# watch_rev3.net
KiCad netlist of a schematic drawn in EAGLE
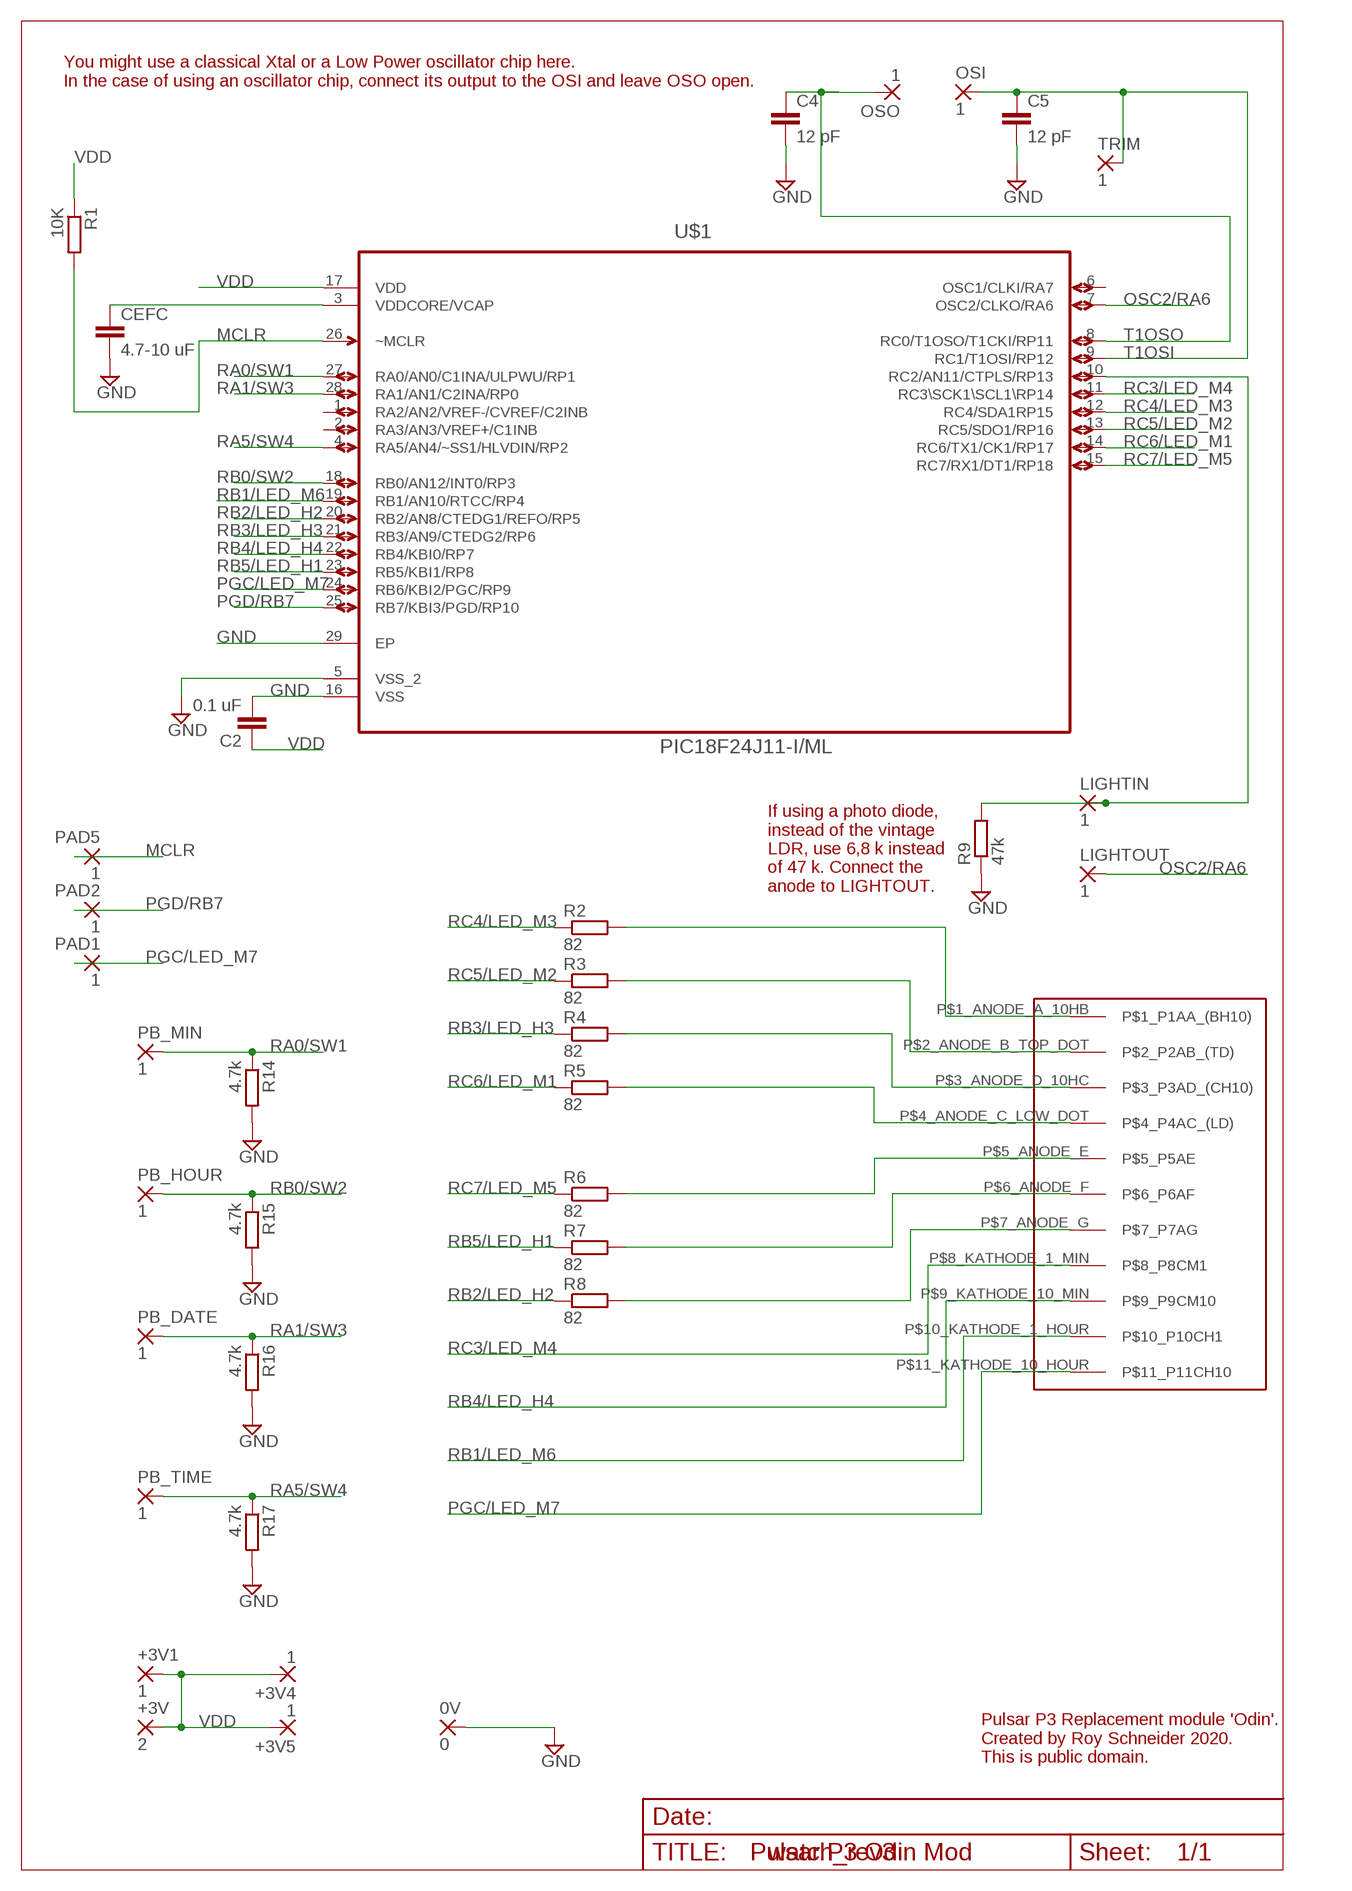
[diagram p0: schematic, sheet 1]

(export (version "E")
  (design (tool "Eeschema 10.0.6"))
  (components
    (comp (ref "+3V")
      (value "2")
      (footprint "eagle-import:SMD1,27-2,54")
      (libsource (lib "eagle-import") (part "SMD2"))
    )
    (comp (ref "+3V1")
      (value "1")
      (footprint "eagle-import:SMD1,27-2,54")
      (libsource (lib "eagle-import") (part "SMD2"))
    )
    (comp (ref "+3V4")
      (value "1")
      (footprint "eagle-import:SMD1,27-2,54")
      (libsource (lib "eagle-import") (part "SMD2"))
    )
    (comp (ref "+3V5")
      (value "1")
      (footprint "eagle-import:SMD1,27-2,54")
      (libsource (lib "eagle-import") (part "SMD2"))
    )
    (comp (ref "0V")
      (value "0")
      (footprint "eagle-import:SMD1,27-2,54")
      (libsource (lib "eagle-import") (part "SMD2"))
    )
    (comp (ref "C2")
      (value "0.1 uF")
      (footprint "eagle-import:C0603")
      (libsource (lib "eagle-import") (part "C-EUC0603"))
    )
    (comp (ref "C4")
      (value "12 pF")
      (footprint "eagle-import:C0603")
      (libsource (lib "eagle-import") (part "C-EUC0603"))
    )
    (comp (ref "C5")
      (value "12 pF")
      (footprint "eagle-import:C0603")
      (libsource (lib "eagle-import") (part "C-EUC0603"))
    )
    (comp (ref "CEFC")
      (value "4.7-10 uF")
      (footprint "eagle-import:C0603")
      (libsource (lib "eagle-import") (part "C-EUC0603"))
    )
    (comp (ref "LIGHTIN")
      (value "1")
      (footprint "eagle-import:SMD1,27-2,54")
      (libsource (lib "eagle-import") (part "SMD2"))
    )
    (comp (ref "LIGHTOUT")
      (value "1")
      (footprint "eagle-import:SMD1,27-2,54")
      (libsource (lib "eagle-import") (part "SMD2"))
    )
    (comp (ref "OSI")
      (value "1")
      (footprint "eagle-import:SMD1,27-2,54")
      (libsource (lib "eagle-import") (part "SMD2"))
    )
    (comp (ref "OSO")
      (value "1")
      (footprint "eagle-import:SMD1,27-2,54")
      (libsource (lib "eagle-import") (part "SMD2"))
    )
    (comp (ref "PAD1")
      (value "1")
      (footprint "eagle-import:SMD1,27-2,54")
      (libsource (lib "eagle-import") (part "SMD2"))
    )
    (comp (ref "PAD2")
      (value "1")
      (footprint "eagle-import:SMD1,27-2,54")
      (libsource (lib "eagle-import") (part "SMD2"))
    )
    (comp (ref "PAD5")
      (value "1")
      (footprint "eagle-import:SMD1,27-2,54")
      (libsource (lib "eagle-import") (part "SMD2"))
    )
    (comp (ref "PB_DATE")
      (value "1")
      (footprint "eagle-import:SMD1,27-2,54")
      (libsource (lib "eagle-import") (part "SMD2"))
    )
    (comp (ref "PB_HOUR")
      (value "1")
      (footprint "eagle-import:SMD1,27-2,54")
      (libsource (lib "eagle-import") (part "SMD2"))
    )
    (comp (ref "PB_MIN")
      (value "1")
      (footprint "eagle-import:SMD1,27-2,54")
      (libsource (lib "eagle-import") (part "SMD2"))
    )
    (comp (ref "PB_TIME")
      (value "1")
      (footprint "eagle-import:SMD1,27-2,54")
      (libsource (lib "eagle-import") (part "SMD2"))
    )
    (comp (ref "R1")
      (value "10K")
      (footprint "eagle-import:R0402")
      (libsource (lib "eagle-import") (part "R-EU_R0402"))
    )
    (comp (ref "R2")
      (value "82")
      (footprint "eagle-import:R0402")
      (libsource (lib "eagle-import") (part "resistor_R-EU_R0402"))
    )
    (comp (ref "R3")
      (value "82")
      (footprint "eagle-import:R0402")
      (libsource (lib "eagle-import") (part "resistor_R-EU_R0402"))
    )
    (comp (ref "R4")
      (value "82")
      (footprint "eagle-import:R0402")
      (libsource (lib "eagle-import") (part "resistor_R-EU_R0402"))
    )
    (comp (ref "R5")
      (value "82")
      (footprint "eagle-import:R0402")
      (libsource (lib "eagle-import") (part "resistor_R-EU_R0402"))
    )
    (comp (ref "R6")
      (value "82")
      (footprint "eagle-import:R0402")
      (libsource (lib "eagle-import") (part "resistor_R-EU_R0402"))
    )
    (comp (ref "R7")
      (value "82")
      (footprint "eagle-import:R0402")
      (libsource (lib "eagle-import") (part "resistor_R-EU_R0402"))
    )
    (comp (ref "R8")
      (value "82")
      (footprint "eagle-import:R0402")
      (libsource (lib "eagle-import") (part "resistor_R-EU_R0402"))
    )
    (comp (ref "R9")
      (value "47k")
      (footprint "eagle-import:R0402")
      (libsource (lib "eagle-import") (part "resistor_R-EU_R0402"))
    )
    (comp (ref "R14")
      (value "4.7k")
      (footprint "eagle-import:R0402")
      (libsource (lib "eagle-import") (part "resistor_R-EU_R0402"))
    )
    (comp (ref "R15")
      (value "4.7k")
      (footprint "eagle-import:R0402")
      (libsource (lib "eagle-import") (part "resistor_R-EU_R0402"))
    )
    (comp (ref "R16")
      (value "4.7k")
      (footprint "eagle-import:R0402")
      (libsource (lib "eagle-import") (part "resistor_R-EU_R0402"))
    )
    (comp (ref "R17")
      (value "4.7k")
      (footprint "eagle-import:R0402")
      (libsource (lib "eagle-import") (part "resistor_R-EU_R0402"))
    )
    (comp (ref "TRIM")
      (value "1")
      (footprint "eagle-import:SMD1,27-2,54")
      (libsource (lib "eagle-import") (part "SMD2"))
    )
    (comp (ref "U$1")
      (value "PIC18F24J11-I/ML")
      (footprint "eagle-import:QFN65P600X600X100-29N")
      (fields (field (name "MPN") "PIC18F24J11-I/Ml"))
      (libsource (lib "eagle-import") (part "PIC18F24J11-I/ML"))
    )
    (comp (ref "U$3")
      (value "PULSAR_P3_DISPLAY")
      (footprint "eagle-import:PULSAR_P3_LED_DISPLAY")
      (libsource (lib "eagle-import") (part "PULSAR_P3_DISPLAY"))
    )
  )
  (nets
    (net (code "1") (name "/MCLR") (class "Default")
      (node (ref "PAD5") (pin "1") (pinfunction "P_1") (pintype "passive"))
      (node (ref "R1") (pin "2") (pinfunction "2_2") (pintype "passive"))
      (node (ref "U$1") (pin "26") (pinfunction "~{MCLR}_26") (pintype "input"))
    )
    (net (code "2") (name "/OSC2{slash}RA6") (class "Default")
      (node (ref "LIGHTOUT") (pin "1") (pinfunction "P_1") (pintype "passive"))
      (node (ref "U$1") (pin "7") (pinfunction "OSC2/CLKO/RA6_7") (pintype "bidirectional"))
    )
    (net (code "3") (name "/PGC{slash}LED_M7") (class "Default")
      (node (ref "PAD1") (pin "1") (pinfunction "P_1") (pintype "passive"))
      (node (ref "U$1") (pin "24") (pinfunction "RB6/KBI2/PGC/RP9_24") (pintype "bidirectional"))
      (node (ref "U$3") (pin "P$11_KATHODE_10_HOUR") (pinfunction "P$11_P11CH10_P$11_KATHODE_10_HOUR") (pintype "bidirectional"))
    )
    (net (code "4") (name "/PGD{slash}RB7") (class "Default")
      (node (ref "PAD2") (pin "1") (pinfunction "P_1") (pintype "passive"))
      (node (ref "U$1") (pin "25") (pinfunction "RB7/KBI3/PGD/RP10_25") (pintype "bidirectional"))
    )
    (net (code "5") (name "/RA0{slash}SW1") (class "Default")
      (node (ref "PB_MIN") (pin "1") (pinfunction "P_1") (pintype "passive"))
      (node (ref "R14") (pin "1") (pinfunction "1_1") (pintype "passive"))
      (node (ref "U$1") (pin "27") (pinfunction "RA0/AN0/C1INA/ULPWU/RP1_27") (pintype "bidirectional"))
    )
    (net (code "6") (name "/RA1{slash}SW3") (class "Default")
      (node (ref "PB_DATE") (pin "1") (pinfunction "P_1") (pintype "passive"))
      (node (ref "R16") (pin "1") (pinfunction "1_1") (pintype "passive"))
      (node (ref "U$1") (pin "28") (pinfunction "RA1/AN1/C2INA/RP0_28") (pintype "bidirectional"))
    )
    (net (code "7") (name "/RA5{slash}SW4") (class "Default")
      (node (ref "PB_TIME") (pin "1") (pinfunction "P_1") (pintype "passive"))
      (node (ref "R17") (pin "1") (pinfunction "1_1") (pintype "passive"))
      (node (ref "U$1") (pin "4") (pinfunction "RA5/AN4/~{SS1/HLVDIN/RP2}_4") (pintype "bidirectional"))
    )
    (net (code "8") (name "/RB0{slash}SW2") (class "Default")
      (node (ref "PB_HOUR") (pin "1") (pinfunction "P_1") (pintype "passive"))
      (node (ref "R15") (pin "1") (pinfunction "1_1") (pintype "passive"))
      (node (ref "U$1") (pin "18") (pinfunction "RB0/AN12/INT0/RP3_18") (pintype "bidirectional"))
    )
    (net (code "9") (name "/RB1{slash}LED_M6") (class "Default")
      (node (ref "U$1") (pin "19") (pinfunction "RB1/AN10/RTCC/RP4_19") (pintype "bidirectional"))
      (node (ref "U$3") (pin "P$10_KATHODE_1_HOUR") (pinfunction "P$10_P10CH1_P$10_KATHODE_1_HOUR") (pintype "bidirectional"))
    )
    (net (code "10") (name "/RB2{slash}LED_H2") (class "Default")
      (node (ref "R8") (pin "1") (pinfunction "1_1") (pintype "passive"))
      (node (ref "U$1") (pin "20") (pinfunction "RB2/AN8/CTEDG1/REFO/RP5_20") (pintype "bidirectional"))
    )
    (net (code "11") (name "/RB3{slash}LED_H3") (class "Default")
      (node (ref "R4") (pin "1") (pinfunction "1_1") (pintype "passive"))
      (node (ref "U$1") (pin "21") (pinfunction "RB3/AN9/CTEDG2/RP6_21") (pintype "bidirectional"))
    )
    (net (code "12") (name "/RB4{slash}LED_H4") (class "Default")
      (node (ref "U$1") (pin "22") (pinfunction "RB4/KBI0/RP7_22") (pintype "bidirectional"))
      (node (ref "U$3") (pin "P$9_KATHODE_10_MIN") (pinfunction "P$9_P9CM10_P$9_KATHODE_10_MIN") (pintype "bidirectional"))
    )
    (net (code "13") (name "/RB5{slash}LED_H1") (class "Default")
      (node (ref "R7") (pin "1") (pinfunction "1_1") (pintype "passive"))
      (node (ref "U$1") (pin "23") (pinfunction "RB5/KBI1/RP8_23") (pintype "bidirectional"))
    )
    (net (code "14") (name "/RC3{slash}LED_M4") (class "Default")
      (node (ref "U$1") (pin "11") (pinfunction "RC3\\SCK1\\SCL1\\RP14_11") (pintype "bidirectional"))
      (node (ref "U$3") (pin "P$8_KATHODE_1_MIN") (pinfunction "P$8_P8CM1_P$8_KATHODE_1_MIN") (pintype "bidirectional"))
    )
    (net (code "15") (name "/RC4{slash}LED_M3") (class "Default")
      (node (ref "R2") (pin "1") (pinfunction "1_1") (pintype "passive"))
      (node (ref "U$1") (pin "12") (pinfunction "RC4/SDA1RP15_12") (pintype "bidirectional"))
    )
    (net (code "16") (name "/RC5{slash}LED_M2") (class "Default")
      (node (ref "R3") (pin "1") (pinfunction "1_1") (pintype "passive"))
      (node (ref "U$1") (pin "13") (pinfunction "RC5/SDO1/RP16_13") (pintype "bidirectional"))
    )
    (net (code "17") (name "/RC6{slash}LED_M1") (class "Default")
      (node (ref "R5") (pin "1") (pinfunction "1_1") (pintype "passive"))
      (node (ref "U$1") (pin "14") (pinfunction "RC6/TX1/CK1/RP17_14") (pintype "bidirectional"))
    )
    (net (code "18") (name "/RC7{slash}LED_M5") (class "Default")
      (node (ref "R6") (pin "1") (pinfunction "1_1") (pintype "passive"))
      (node (ref "U$1") (pin "15") (pinfunction "RC7/RX1/DT1/RP18_15") (pintype "bidirectional"))
    )
    (net (code "19") (name "/T1OSI") (class "Default")
      (node (ref "C5") (pin "1") (pinfunction "1_1") (pintype "passive"))
      (node (ref "OSI") (pin "1") (pinfunction "P_1") (pintype "passive"))
      (node (ref "TRIM") (pin "1") (pinfunction "P_1") (pintype "passive"))
      (node (ref "U$1") (pin "9") (pinfunction "RC1/T1OSI/RP12_9") (pintype "bidirectional"))
    )
    (net (code "20") (name "/T1OSO") (class "Default")
      (node (ref "C4") (pin "1") (pinfunction "1_1") (pintype "passive"))
      (node (ref "OSO") (pin "1") (pinfunction "P_1") (pintype "passive"))
      (node (ref "U$1") (pin "8") (pinfunction "RC0/T1OSO/T1CKI/RP11_8") (pintype "bidirectional"))
    )
    (net (code "21") (name "/VDD") (class "Default")
      (node (ref "+3V") (pin "1") (pinfunction "P_1") (pintype "passive"))
      (node (ref "+3V1") (pin "1") (pinfunction "P_1") (pintype "passive"))
      (node (ref "+3V4") (pin "1") (pinfunction "P_1") (pintype "passive"))
      (node (ref "+3V5") (pin "1") (pinfunction "P_1") (pintype "passive"))
      (node (ref "C2") (pin "1") (pinfunction "1_1") (pintype "passive"))
      (node (ref "R1") (pin "1") (pinfunction "1_1") (pintype "passive"))
      (node (ref "U$1") (pin "17") (pinfunction "VDD_17") (pintype "power_in"))
    )
    (net (code "22") (name "GND") (class "Default")
      (node (ref "0V") (pin "1") (pinfunction "P_1") (pintype "passive"))
      (node (ref "C2") (pin "2") (pinfunction "2_2") (pintype "passive"))
      (node (ref "C4") (pin "2") (pinfunction "2_2") (pintype "passive"))
      (node (ref "C5") (pin "2") (pinfunction "2_2") (pintype "passive"))
      (node (ref "CEFC") (pin "2") (pinfunction "2_2") (pintype "passive"))
      (node (ref "R14") (pin "2") (pinfunction "2_2") (pintype "passive"))
      (node (ref "R15") (pin "2") (pinfunction "2_2") (pintype "passive"))
      (node (ref "R16") (pin "2") (pinfunction "2_2") (pintype "passive"))
      (node (ref "R17") (pin "2") (pinfunction "2_2") (pintype "passive"))
      (node (ref "R9") (pin "1") (pinfunction "1_1") (pintype "passive"))
      (node (ref "U$1") (pin "16") (pinfunction "VSS_16") (pintype "passive"))
      (node (ref "U$1") (pin "29") (pinfunction "EP_29") (pintype "passive"))
      (node (ref "U$1") (pin "5") (pinfunction "VSS_2_5") (pintype "passive"))
    )
    (net (code "23") (name "Net-(LIGHTIN-P)") (class "Default")
      (node (ref "LIGHTIN") (pin "1") (pinfunction "P_1") (pintype "passive"))
      (node (ref "R9") (pin "2") (pinfunction "2_2") (pintype "passive"))
      (node (ref "U$1") (pin "10") (pinfunction "RC2/AN11/CTPLS/RP13_10") (pintype "bidirectional"))
    )
    (net (code "24") (name "Net-(U$1-VDDCORE{slash}VCAP)") (class "Default")
      (node (ref "CEFC") (pin "1") (pinfunction "1_1") (pintype "passive"))
      (node (ref "U$1") (pin "3") (pinfunction "VDDCORE/VCAP_3") (pintype "power_in"))
    )
    (net (code "25") (name "Net-(U$3-P$1_P1AA_(BH10))") (class "Default")
      (node (ref "R2") (pin "2") (pinfunction "2_2") (pintype "passive"))
      (node (ref "U$3") (pin "P$1_ANODE_A_10HB") (pinfunction "P$1_P1AA_(BH10)_P$1_ANODE_A_10HB") (pintype "bidirectional"))
    )
    (net (code "26") (name "Net-(U$3-P$2_P2AB_(TD))") (class "Default")
      (node (ref "R3") (pin "2") (pinfunction "2_2") (pintype "passive"))
      (node (ref "U$3") (pin "P$2_ANODE_B_TOP_DOT") (pinfunction "P$2_P2AB_(TD)_P$2_ANODE_B_TOP_DOT") (pintype "bidirectional"))
    )
    (net (code "27") (name "Net-(U$3-P$3_P3AD_(CH10))") (class "Default")
      (node (ref "R4") (pin "2") (pinfunction "2_2") (pintype "passive"))
      (node (ref "U$3") (pin "P$3_ANODE_D_10HC") (pinfunction "P$3_P3AD_(CH10)_P$3_ANODE_D_10HC") (pintype "bidirectional"))
    )
    (net (code "28") (name "Net-(U$3-P$4_P4AC_(LD))") (class "Default")
      (node (ref "R5") (pin "2") (pinfunction "2_2") (pintype "passive"))
      (node (ref "U$3") (pin "P$4_ANODE_C_LOW_DOT") (pinfunction "P$4_P4AC_(LD)_P$4_ANODE_C_LOW_DOT") (pintype "bidirectional"))
    )
    (net (code "29") (name "Net-(U$3-P$5_P5AE)") (class "Default")
      (node (ref "R6") (pin "2") (pinfunction "2_2") (pintype "passive"))
      (node (ref "U$3") (pin "P$5_ANODE_E") (pinfunction "P$5_P5AE_P$5_ANODE_E") (pintype "bidirectional"))
    )
    (net (code "30") (name "Net-(U$3-P$6_P6AF)") (class "Default")
      (node (ref "R7") (pin "2") (pinfunction "2_2") (pintype "passive"))
      (node (ref "U$3") (pin "P$6_ANODE_F") (pinfunction "P$6_P6AF_P$6_ANODE_F") (pintype "bidirectional"))
    )
    (net (code "31") (name "Net-(U$3-P$7_P7AG)") (class "Default")
      (node (ref "R8") (pin "2") (pinfunction "2_2") (pintype "passive"))
      (node (ref "U$3") (pin "P$7_ANODE_G") (pinfunction "P$7_P7AG_P$7_ANODE_G") (pintype "bidirectional"))
    )
    (net (code "32") (name "unconnected-(U$1-OSC1{slash}CLKI{slash}RA7-Pad6)") (class "Default")
      (node (ref "U$1") (pin "6") (pinfunction "OSC1/CLKI/RA7_6") (pintype "bidirectional"))
    )
    (net (code "33") (name "unconnected-(U$1-RA2{slash}AN2{slash}VREF-{slash}CVREF{slash}C2INB-Pad1)") (class "Default")
      (node (ref "U$1") (pin "1") (pinfunction "RA2/AN2/VREF-/CVREF/C2INB_1") (pintype "bidirectional"))
    )
    (net (code "34") (name "unconnected-(U$1-RA3{slash}AN3{slash}VREF+{slash}C1INB-Pad2)") (class "Default")
      (node (ref "U$1") (pin "2") (pinfunction "RA3/AN3/VREF+/C1INB_2") (pintype "bidirectional"))
    )
  )
)
